# Mosfet_Board.net
KiCad netlist of a schematic drawn in Altium Designer
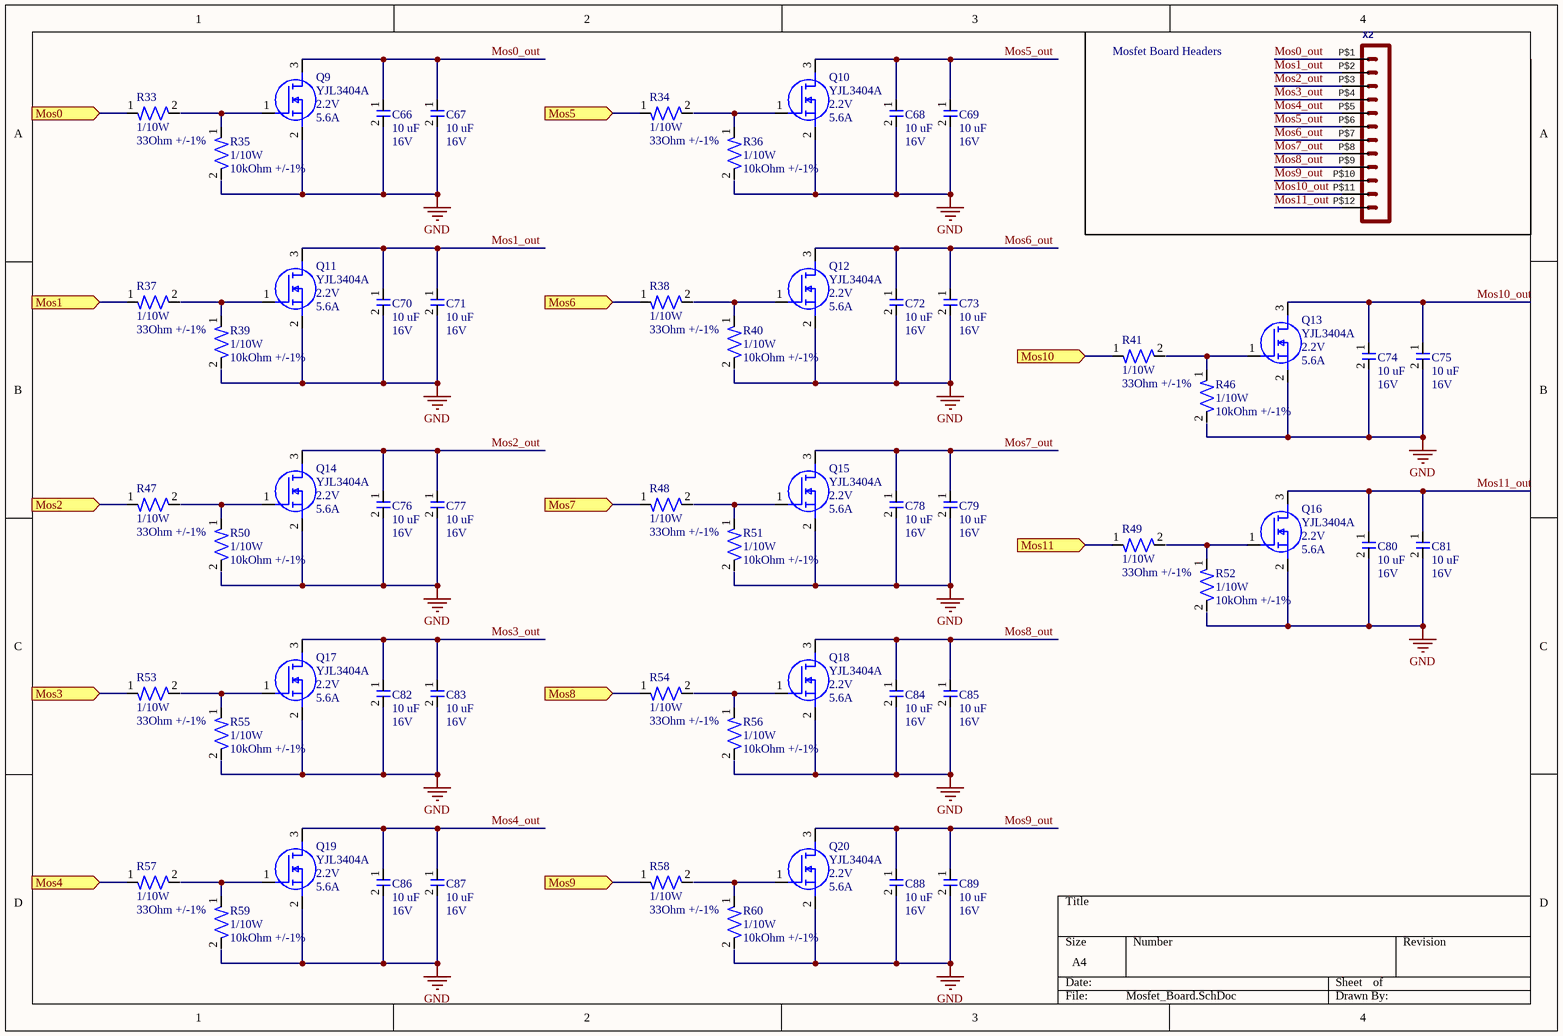
[diagram p0: Mosfet_Board.SchDoc]

(export (version "E")
  (design (tool "Eeschema 10.0.6"))
  (components
    (comp (ref "C66")
      (value "MCS1802GS-20-Z")
      (footprint "CAP-0805")
      (description "10 µF ±10% 16V Ceramic Capacitor X7R 0805 (2012 Metric)")
      (fields (field (name "CAPACITANCE") "10 uF") (field (name "VOLTAGE RATING") "16V"))
      (libsource (lib "MasterLib") (part "CAP-10U-0002"))
    )
    (comp (ref "C67")
      (value "MCS1802GS-20-Z")
      (footprint "CAP-0805")
      (description "10 µF ±10% 16V Ceramic Capacitor X7R 0805 (2012 Metric)")
      (fields (field (name "CAPACITANCE") "10 uF") (field (name "VOLTAGE RATING") "16V"))
      (libsource (lib "MasterLib") (part "CAP-10U-0002"))
    )
    (comp (ref "C68")
      (value "MCS1802GS-20-Z")
      (footprint "CAP-0805")
      (description "10 µF ±10% 16V Ceramic Capacitor X7R 0805 (2012 Metric)")
      (fields (field (name "CAPACITANCE") "10 uF") (field (name "VOLTAGE RATING") "16V"))
      (libsource (lib "MasterLib") (part "CAP-10U-0002"))
    )
    (comp (ref "C69")
      (value "MCS1802GS-20-Z")
      (footprint "CAP-0805")
      (description "10 µF ±10% 16V Ceramic Capacitor X7R 0805 (2012 Metric)")
      (fields (field (name "CAPACITANCE") "10 uF") (field (name "VOLTAGE RATING") "16V"))
      (libsource (lib "MasterLib") (part "CAP-10U-0002"))
    )
    (comp (ref "C70")
      (value "MCS1802GS-20-Z")
      (footprint "CAP-0805")
      (description "10 µF ±10% 16V Ceramic Capacitor X7R 0805 (2012 Metric)")
      (fields (field (name "CAPACITANCE") "10 uF") (field (name "VOLTAGE RATING") "16V"))
      (libsource (lib "MasterLib") (part "CAP-10U-0002"))
    )
    (comp (ref "C71")
      (value "MCS1802GS-20-Z")
      (footprint "CAP-0805")
      (description "10 µF ±10% 16V Ceramic Capacitor X7R 0805 (2012 Metric)")
      (fields (field (name "CAPACITANCE") "10 uF") (field (name "VOLTAGE RATING") "16V"))
      (libsource (lib "MasterLib") (part "CAP-10U-0002"))
    )
    (comp (ref "C72")
      (value "MCS1802GS-20-Z")
      (footprint "CAP-0805")
      (description "10 µF ±10% 16V Ceramic Capacitor X7R 0805 (2012 Metric)")
      (fields (field (name "CAPACITANCE") "10 uF") (field (name "VOLTAGE RATING") "16V"))
      (libsource (lib "MasterLib") (part "CAP-10U-0002"))
    )
    (comp (ref "C73")
      (value "MCS1802GS-20-Z")
      (footprint "CAP-0805")
      (description "10 µF ±10% 16V Ceramic Capacitor X7R 0805 (2012 Metric)")
      (fields (field (name "CAPACITANCE") "10 uF") (field (name "VOLTAGE RATING") "16V"))
      (libsource (lib "MasterLib") (part "CAP-10U-0002"))
    )
    (comp (ref "C74")
      (value "MCS1802GS-20-Z")
      (footprint "CAP-0805")
      (description "10 µF ±10% 16V Ceramic Capacitor X7R 0805 (2012 Metric)")
      (fields (field (name "CAPACITANCE") "10 uF") (field (name "VOLTAGE RATING") "16V"))
      (libsource (lib "MasterLib") (part "CAP-10U-0002"))
    )
    (comp (ref "C75")
      (value "MCS1802GS-20-Z")
      (footprint "CAP-0805")
      (description "10 µF ±10% 16V Ceramic Capacitor X7R 0805 (2012 Metric)")
      (fields (field (name "CAPACITANCE") "10 uF") (field (name "VOLTAGE RATING") "16V"))
      (libsource (lib "MasterLib") (part "CAP-10U-0002"))
    )
    (comp (ref "C76")
      (value "MCS1802GS-20-Z")
      (footprint "CAP-0805")
      (description "10 µF ±10% 16V Ceramic Capacitor X7R 0805 (2012 Metric)")
      (fields (field (name "CAPACITANCE") "10 uF") (field (name "VOLTAGE RATING") "16V"))
      (libsource (lib "MasterLib") (part "CAP-10U-0002"))
    )
    (comp (ref "C77")
      (value "MCS1802GS-20-Z")
      (footprint "CAP-0805")
      (description "10 µF ±10% 16V Ceramic Capacitor X7R 0805 (2012 Metric)")
      (fields (field (name "CAPACITANCE") "10 uF") (field (name "VOLTAGE RATING") "16V"))
      (libsource (lib "MasterLib") (part "CAP-10U-0002"))
    )
    (comp (ref "C78")
      (value "MCS1802GS-20-Z")
      (footprint "CAP-0805")
      (description "10 µF ±10% 16V Ceramic Capacitor X7R 0805 (2012 Metric)")
      (fields (field (name "CAPACITANCE") "10 uF") (field (name "VOLTAGE RATING") "16V"))
      (libsource (lib "MasterLib") (part "CAP-10U-0002"))
    )
    (comp (ref "C79")
      (value "MCS1802GS-20-Z")
      (footprint "CAP-0805")
      (description "10 µF ±10% 16V Ceramic Capacitor X7R 0805 (2012 Metric)")
      (fields (field (name "CAPACITANCE") "10 uF") (field (name "VOLTAGE RATING") "16V"))
      (libsource (lib "MasterLib") (part "CAP-10U-0002"))
    )
    (comp (ref "C80")
      (value "MCS1802GS-20-Z")
      (footprint "CAP-0805")
      (description "10 µF ±10% 16V Ceramic Capacitor X7R 0805 (2012 Metric)")
      (fields (field (name "CAPACITANCE") "10 uF") (field (name "VOLTAGE RATING") "16V"))
      (libsource (lib "MasterLib") (part "CAP-10U-0002"))
    )
    (comp (ref "C81")
      (value "MCS1802GS-20-Z")
      (footprint "CAP-0805")
      (description "10 µF ±10% 16V Ceramic Capacitor X7R 0805 (2012 Metric)")
      (fields (field (name "CAPACITANCE") "10 uF") (field (name "VOLTAGE RATING") "16V"))
      (libsource (lib "MasterLib") (part "CAP-10U-0002"))
    )
    (comp (ref "C82")
      (value "MCS1802GS-20-Z")
      (footprint "CAP-0805")
      (description "10 µF ±10% 16V Ceramic Capacitor X7R 0805 (2012 Metric)")
      (fields (field (name "CAPACITANCE") "10 uF") (field (name "VOLTAGE RATING") "16V"))
      (libsource (lib "MasterLib") (part "CAP-10U-0002"))
    )
    (comp (ref "C83")
      (value "MCS1802GS-20-Z")
      (footprint "CAP-0805")
      (description "10 µF ±10% 16V Ceramic Capacitor X7R 0805 (2012 Metric)")
      (fields (field (name "CAPACITANCE") "10 uF") (field (name "VOLTAGE RATING") "16V"))
      (libsource (lib "MasterLib") (part "CAP-10U-0002"))
    )
    (comp (ref "C84")
      (value "MCS1802GS-20-Z")
      (footprint "CAP-0805")
      (description "10 µF ±10% 16V Ceramic Capacitor X7R 0805 (2012 Metric)")
      (fields (field (name "CAPACITANCE") "10 uF") (field (name "VOLTAGE RATING") "16V"))
      (libsource (lib "MasterLib") (part "CAP-10U-0002"))
    )
    (comp (ref "C85")
      (value "MCS1802GS-20-Z")
      (footprint "CAP-0805")
      (description "10 µF ±10% 16V Ceramic Capacitor X7R 0805 (2012 Metric)")
      (fields (field (name "CAPACITANCE") "10 uF") (field (name "VOLTAGE RATING") "16V"))
      (libsource (lib "MasterLib") (part "CAP-10U-0002"))
    )
    (comp (ref "C86")
      (value "MCS1802GS-20-Z")
      (footprint "CAP-0805")
      (description "10 µF ±10% 16V Ceramic Capacitor X7R 0805 (2012 Metric)")
      (fields (field (name "CAPACITANCE") "10 uF") (field (name "VOLTAGE RATING") "16V"))
      (libsource (lib "MasterLib") (part "CAP-10U-0002"))
    )
    (comp (ref "C87")
      (value "MCS1802GS-20-Z")
      (footprint "CAP-0805")
      (description "10 µF ±10% 16V Ceramic Capacitor X7R 0805 (2012 Metric)")
      (fields (field (name "CAPACITANCE") "10 uF") (field (name "VOLTAGE RATING") "16V"))
      (libsource (lib "MasterLib") (part "CAP-10U-0002"))
    )
    (comp (ref "C88")
      (value "MCS1802GS-20-Z")
      (footprint "CAP-0805")
      (description "10 µF ±10% 16V Ceramic Capacitor X7R 0805 (2012 Metric)")
      (fields (field (name "CAPACITANCE") "10 uF") (field (name "VOLTAGE RATING") "16V"))
      (libsource (lib "MasterLib") (part "CAP-10U-0002"))
    )
    (comp (ref "C89")
      (value "MCS1802GS-20-Z")
      (footprint "CAP-0805")
      (description "10 µF ±10% 16V Ceramic Capacitor X7R 0805 (2012 Metric)")
      (fields (field (name "CAPACITANCE") "10 uF") (field (name "VOLTAGE RATING") "16V"))
      (libsource (lib "MasterLib") (part "CAP-10U-0002"))
    )
    (comp (ref "Q9")
      (value "YJL3404A")
      (footprint "NMOS-SOT23-3")
      (description "N-Channel 30 V 5.6A (Ta) 1.2W (Ta) Surface Mount SOT-23")
      (fields (field (name "VGS(TH)") "2.2V") (field (name "DRAIN CURRENT") "5.6A"))
      (libsource (lib "MasterLib") (part "NMOS-5.6A-0001"))
    )
    (comp (ref "Q10")
      (value "YJL3404A")
      (footprint "NMOS-SOT23-3")
      (description "N-Channel 30 V 5.6A (Ta) 1.2W (Ta) Surface Mount SOT-23")
      (fields (field (name "VGS(TH)") "2.2V") (field (name "DRAIN CURRENT") "5.6A"))
      (libsource (lib "MasterLib") (part "NMOS-5.6A-0001"))
    )
    (comp (ref "Q11")
      (value "YJL3404A")
      (footprint "NMOS-SOT23-3")
      (description "N-Channel 30 V 5.6A (Ta) 1.2W (Ta) Surface Mount SOT-23")
      (fields (field (name "VGS(TH)") "2.2V") (field (name "DRAIN CURRENT") "5.6A"))
      (libsource (lib "MasterLib") (part "NMOS-5.6A-0001"))
    )
    (comp (ref "Q12")
      (value "YJL3404A")
      (footprint "NMOS-SOT23-3")
      (description "N-Channel 30 V 5.6A (Ta) 1.2W (Ta) Surface Mount SOT-23")
      (fields (field (name "VGS(TH)") "2.2V") (field (name "DRAIN CURRENT") "5.6A"))
      (libsource (lib "MasterLib") (part "NMOS-5.6A-0001"))
    )
    (comp (ref "Q13")
      (value "YJL3404A")
      (footprint "NMOS-SOT23-3")
      (description "N-Channel 30 V 5.6A (Ta) 1.2W (Ta) Surface Mount SOT-23")
      (fields (field (name "VGS(TH)") "2.2V") (field (name "DRAIN CURRENT") "5.6A"))
      (libsource (lib "MasterLib") (part "NMOS-5.6A-0001"))
    )
    (comp (ref "Q14")
      (value "YJL3404A")
      (footprint "NMOS-SOT23-3")
      (description "N-Channel 30 V 5.6A (Ta) 1.2W (Ta) Surface Mount SOT-23")
      (fields (field (name "VGS(TH)") "2.2V") (field (name "DRAIN CURRENT") "5.6A"))
      (libsource (lib "MasterLib") (part "NMOS-5.6A-0001"))
    )
    (comp (ref "Q15")
      (value "YJL3404A")
      (footprint "NMOS-SOT23-3")
      (description "N-Channel 30 V 5.6A (Ta) 1.2W (Ta) Surface Mount SOT-23")
      (fields (field (name "VGS(TH)") "2.2V") (field (name "DRAIN CURRENT") "5.6A"))
      (libsource (lib "MasterLib") (part "NMOS-5.6A-0001"))
    )
    (comp (ref "Q16")
      (value "YJL3404A")
      (footprint "NMOS-SOT23-3")
      (description "N-Channel 30 V 5.6A (Ta) 1.2W (Ta) Surface Mount SOT-23")
      (fields (field (name "VGS(TH)") "2.2V") (field (name "DRAIN CURRENT") "5.6A"))
      (libsource (lib "MasterLib") (part "NMOS-5.6A-0001"))
    )
    (comp (ref "Q17")
      (value "YJL3404A")
      (footprint "NMOS-SOT23-3")
      (description "N-Channel 30 V 5.6A (Ta) 1.2W (Ta) Surface Mount SOT-23")
      (fields (field (name "VGS(TH)") "2.2V") (field (name "DRAIN CURRENT") "5.6A"))
      (libsource (lib "MasterLib") (part "NMOS-5.6A-0001"))
    )
    (comp (ref "Q18")
      (value "YJL3404A")
      (footprint "NMOS-SOT23-3")
      (description "N-Channel 30 V 5.6A (Ta) 1.2W (Ta) Surface Mount SOT-23")
      (fields (field (name "VGS(TH)") "2.2V") (field (name "DRAIN CURRENT") "5.6A"))
      (libsource (lib "MasterLib") (part "NMOS-5.6A-0001"))
    )
    (comp (ref "Q19")
      (value "YJL3404A")
      (footprint "NMOS-SOT23-3")
      (description "N-Channel 30 V 5.6A (Ta) 1.2W (Ta) Surface Mount SOT-23")
      (fields (field (name "VGS(TH)") "2.2V") (field (name "DRAIN CURRENT") "5.6A"))
      (libsource (lib "MasterLib") (part "NMOS-5.6A-0001"))
    )
    (comp (ref "Q20")
      (value "YJL3404A")
      (footprint "NMOS-SOT23-3")
      (description "N-Channel 30 V 5.6A (Ta) 1.2W (Ta) Surface Mount SOT-23")
      (fields (field (name "VGS(TH)") "2.2V") (field (name "DRAIN CURRENT") "5.6A"))
      (libsource (lib "MasterLib") (part "NMOS-5.6A-0001"))
    )
    (comp (ref "R33")
      (value "RC0603FR-0733RP")
      (footprint "RES-0603")
      (description "RES SMD 33 OHM 1% 1/10W 0603")
      (fields
        (field (name "MANUFACTURER") "YAGEO")
        (field (name "POWER RATING") "1/10W")
        (field (name "RESISTANCE") "33Ohm +/-1%")
      )
      (libsource (lib "MasterLib") (part "RES-33-0002"))
    )
    (comp (ref "R34")
      (value "RC0603FR-0733RP")
      (footprint "RES-0603")
      (description "RES SMD 33 OHM 1% 1/10W 0603")
      (fields
        (field (name "MANUFACTURER") "YAGEO")
        (field (name "POWER RATING") "1/10W")
        (field (name "RESISTANCE") "33Ohm +/-1%")
      )
      (libsource (lib "MasterLib") (part "RES-33-0002"))
    )
    (comp (ref "R35")
      (value "RC0603FR-0710KP")
      (footprint "RES-0603")
      (description "RES SMD 10K OHM 1% 1/10W 0603")
      (fields
        (field (name "MANUFACTURER") "YAGEO")
        (field (name "POWER RATING") "1/10W")
        (field (name "RESISTANCE") "10kOhm +/-1%")
      )
      (libsource (lib "MasterLib") (part "RES-10K-0002"))
    )
    (comp (ref "R36")
      (value "RC0603FR-0710KP")
      (footprint "RES-0603")
      (description "RES SMD 10K OHM 1% 1/10W 0603")
      (fields
        (field (name "MANUFACTURER") "YAGEO")
        (field (name "POWER RATING") "1/10W")
        (field (name "RESISTANCE") "10kOhm +/-1%")
      )
      (libsource (lib "MasterLib") (part "RES-10K-0002"))
    )
    (comp (ref "R37")
      (value "RC0603FR-0733RP")
      (footprint "RES-0603")
      (description "RES SMD 33 OHM 1% 1/10W 0603")
      (fields
        (field (name "MANUFACTURER") "YAGEO")
        (field (name "POWER RATING") "1/10W")
        (field (name "RESISTANCE") "33Ohm +/-1%")
      )
      (libsource (lib "MasterLib") (part "RES-33-0002"))
    )
    (comp (ref "R38")
      (value "RC0603FR-0733RP")
      (footprint "RES-0603")
      (description "RES SMD 33 OHM 1% 1/10W 0603")
      (fields
        (field (name "MANUFACTURER") "YAGEO")
        (field (name "POWER RATING") "1/10W")
        (field (name "RESISTANCE") "33Ohm +/-1%")
      )
      (libsource (lib "MasterLib") (part "RES-33-0002"))
    )
    (comp (ref "R39")
      (value "RC0603FR-0710KP")
      (footprint "RES-0603")
      (description "RES SMD 10K OHM 1% 1/10W 0603")
      (fields
        (field (name "MANUFACTURER") "YAGEO")
        (field (name "POWER RATING") "1/10W")
        (field (name "RESISTANCE") "10kOhm +/-1%")
      )
      (libsource (lib "MasterLib") (part "RES-10K-0002"))
    )
    (comp (ref "R40")
      (value "RC0603FR-0710KP")
      (footprint "RES-0603")
      (description "RES SMD 10K OHM 1% 1/10W 0603")
      (fields
        (field (name "MANUFACTURER") "YAGEO")
        (field (name "POWER RATING") "1/10W")
        (field (name "RESISTANCE") "10kOhm +/-1%")
      )
      (libsource (lib "MasterLib") (part "RES-10K-0002"))
    )
    (comp (ref "R41")
      (value "RC0603FR-0733RP")
      (footprint "RES-0603")
      (description "RES SMD 33 OHM 1% 1/10W 0603")
      (fields
        (field (name "MANUFACTURER") "YAGEO")
        (field (name "POWER RATING") "1/10W")
        (field (name "RESISTANCE") "33Ohm +/-1%")
      )
      (libsource (lib "MasterLib") (part "RES-33-0002"))
    )
    (comp (ref "R46")
      (value "RC0603FR-0710KP")
      (footprint "RES-0603")
      (description "RES SMD 10K OHM 1% 1/10W 0603")
      (fields
        (field (name "MANUFACTURER") "YAGEO")
        (field (name "POWER RATING") "1/10W")
        (field (name "RESISTANCE") "10kOhm +/-1%")
      )
      (libsource (lib "MasterLib") (part "RES-10K-0002"))
    )
    (comp (ref "R47")
      (value "RC0603FR-0733RP")
      (footprint "RES-0603")
      (description "RES SMD 33 OHM 1% 1/10W 0603")
      (fields
        (field (name "MANUFACTURER") "YAGEO")
        (field (name "POWER RATING") "1/10W")
        (field (name "RESISTANCE") "33Ohm +/-1%")
      )
      (libsource (lib "MasterLib") (part "RES-33-0002"))
    )
    (comp (ref "R48")
      (value "RC0603FR-0733RP")
      (footprint "RES-0603")
      (description "RES SMD 33 OHM 1% 1/10W 0603")
      (fields
        (field (name "MANUFACTURER") "YAGEO")
        (field (name "POWER RATING") "1/10W")
        (field (name "RESISTANCE") "33Ohm +/-1%")
      )
      (libsource (lib "MasterLib") (part "RES-33-0002"))
    )
    (comp (ref "R49")
      (value "RC0603FR-0733RP")
      (footprint "RES-0603")
      (description "RES SMD 33 OHM 1% 1/10W 0603")
      (fields
        (field (name "MANUFACTURER") "YAGEO")
        (field (name "POWER RATING") "1/10W")
        (field (name "RESISTANCE") "33Ohm +/-1%")
      )
      (libsource (lib "MasterLib") (part "RES-33-0002"))
    )
    (comp (ref "R50")
      (value "RC0603FR-0710KP")
      (footprint "RES-0603")
      (description "RES SMD 10K OHM 1% 1/10W 0603")
      (fields
        (field (name "MANUFACTURER") "YAGEO")
        (field (name "POWER RATING") "1/10W")
        (field (name "RESISTANCE") "10kOhm +/-1%")
      )
      (libsource (lib "MasterLib") (part "RES-10K-0002"))
    )
    (comp (ref "R51")
      (value "RC0603FR-0710KP")
      (footprint "RES-0603")
      (description "RES SMD 10K OHM 1% 1/10W 0603")
      (fields
        (field (name "MANUFACTURER") "YAGEO")
        (field (name "POWER RATING") "1/10W")
        (field (name "RESISTANCE") "10kOhm +/-1%")
      )
      (libsource (lib "MasterLib") (part "RES-10K-0002"))
    )
    (comp (ref "R52")
      (value "RC0603FR-0710KP")
      (footprint "RES-0603")
      (description "RES SMD 10K OHM 1% 1/10W 0603")
      (fields
        (field (name "MANUFACTURER") "YAGEO")
        (field (name "POWER RATING") "1/10W")
        (field (name "RESISTANCE") "10kOhm +/-1%")
      )
      (libsource (lib "MasterLib") (part "RES-10K-0002"))
    )
    (comp (ref "R53")
      (value "RC0603FR-0733RP")
      (footprint "RES-0603")
      (description "RES SMD 33 OHM 1% 1/10W 0603")
      (fields
        (field (name "MANUFACTURER") "YAGEO")
        (field (name "POWER RATING") "1/10W")
        (field (name "RESISTANCE") "33Ohm +/-1%")
      )
      (libsource (lib "MasterLib") (part "RES-33-0002"))
    )
    (comp (ref "R54")
      (value "RC0603FR-0733RP")
      (footprint "RES-0603")
      (description "RES SMD 33 OHM 1% 1/10W 0603")
      (fields
        (field (name "MANUFACTURER") "YAGEO")
        (field (name "POWER RATING") "1/10W")
        (field (name "RESISTANCE") "33Ohm +/-1%")
      )
      (libsource (lib "MasterLib") (part "RES-33-0002"))
    )
    (comp (ref "R55")
      (value "RC0603FR-0710KP")
      (footprint "RES-0603")
      (description "RES SMD 10K OHM 1% 1/10W 0603")
      (fields
        (field (name "MANUFACTURER") "YAGEO")
        (field (name "POWER RATING") "1/10W")
        (field (name "RESISTANCE") "10kOhm +/-1%")
      )
      (libsource (lib "MasterLib") (part "RES-10K-0002"))
    )
    (comp (ref "R56")
      (value "RC0603FR-0710KP")
      (footprint "RES-0603")
      (description "RES SMD 10K OHM 1% 1/10W 0603")
      (fields
        (field (name "MANUFACTURER") "YAGEO")
        (field (name "POWER RATING") "1/10W")
        (field (name "RESISTANCE") "10kOhm +/-1%")
      )
      (libsource (lib "MasterLib") (part "RES-10K-0002"))
    )
    (comp (ref "R57")
      (value "RC0603FR-0733RP")
      (footprint "RES-0603")
      (description "RES SMD 33 OHM 1% 1/10W 0603")
      (fields
        (field (name "MANUFACTURER") "YAGEO")
        (field (name "POWER RATING") "1/10W")
        (field (name "RESISTANCE") "33Ohm +/-1%")
      )
      (libsource (lib "MasterLib") (part "RES-33-0002"))
    )
    (comp (ref "R58")
      (value "RC0603FR-0733RP")
      (footprint "RES-0603")
      (description "RES SMD 33 OHM 1% 1/10W 0603")
      (fields
        (field (name "MANUFACTURER") "YAGEO")
        (field (name "POWER RATING") "1/10W")
        (field (name "RESISTANCE") "33Ohm +/-1%")
      )
      (libsource (lib "MasterLib") (part "RES-33-0002"))
    )
    (comp (ref "R59")
      (value "RC0603FR-0710KP")
      (footprint "RES-0603")
      (description "RES SMD 10K OHM 1% 1/10W 0603")
      (fields
        (field (name "MANUFACTURER") "YAGEO")
        (field (name "POWER RATING") "1/10W")
        (field (name "RESISTANCE") "10kOhm +/-1%")
      )
      (libsource (lib "MasterLib") (part "RES-10K-0002"))
    )
    (comp (ref "R60")
      (value "RC0603FR-0710KP")
      (footprint "RES-0603")
      (description "RES SMD 10K OHM 1% 1/10W 0603")
      (fields
        (field (name "MANUFACTURER") "YAGEO")
        (field (name "POWER RATING") "1/10W")
        (field (name "RESISTANCE") "10kOhm +/-1%")
      )
      (libsource (lib "MasterLib") (part "RES-10K-0002"))
    )
    (comp (ref "X2")
      (value "Molex - Micro-Fit 3.0 Series connector,  3.00mm (0.118\") pitch header, 12 positions.")
      (footprint "44764-1201")
      (libsource (lib "Molex Microfit") (part "HEADER_POS12_?44764-1201"))
    )
  )
  (nets
    (net (code "1") (name "/Mos0") (class "Default")
      (node (ref "R33") (pin "1") (pinfunction "1_1") (pintype "passive"))
    )
    (net (code "2") (name "/Mos0_out") (class "Default")
      (node (ref "C66") (pin "1") (pinfunction "1_1") (pintype "passive"))
      (node (ref "C67") (pin "1") (pinfunction "1_1") (pintype "passive"))
      (node (ref "Q9") (pin "3") (pinfunction "D_3") (pintype "passive"))
      (node (ref "X2") (pin "P$1") (pinfunction "1_P$1") (pintype "passive"))
    )
    (net (code "3") (name "/Mos1") (class "Default")
      (node (ref "R37") (pin "1") (pinfunction "1_1") (pintype "passive"))
    )
    (net (code "4") (name "/Mos1_out") (class "Default")
      (node (ref "C70") (pin "1") (pinfunction "1_1") (pintype "passive"))
      (node (ref "C71") (pin "1") (pinfunction "1_1") (pintype "passive"))
      (node (ref "Q11") (pin "3") (pinfunction "D_3") (pintype "passive"))
      (node (ref "X2") (pin "P$2") (pinfunction "2_P$2") (pintype "passive"))
    )
    (net (code "5") (name "/Mos2") (class "Default")
      (node (ref "R47") (pin "1") (pinfunction "1_1") (pintype "passive"))
    )
    (net (code "6") (name "/Mos2_out") (class "Default")
      (node (ref "C76") (pin "1") (pinfunction "1_1") (pintype "passive"))
      (node (ref "C77") (pin "1") (pinfunction "1_1") (pintype "passive"))
      (node (ref "Q14") (pin "3") (pinfunction "D_3") (pintype "passive"))
      (node (ref "X2") (pin "P$3") (pinfunction "3_P$3") (pintype "passive"))
    )
    (net (code "7") (name "/Mos3") (class "Default")
      (node (ref "R53") (pin "1") (pinfunction "1_1") (pintype "passive"))
    )
    (net (code "8") (name "/Mos3_out") (class "Default")
      (node (ref "C82") (pin "1") (pinfunction "1_1") (pintype "passive"))
      (node (ref "C83") (pin "1") (pinfunction "1_1") (pintype "passive"))
      (node (ref "Q17") (pin "3") (pinfunction "D_3") (pintype "passive"))
      (node (ref "X2") (pin "P$4") (pinfunction "4_P$4") (pintype "passive"))
    )
    (net (code "9") (name "/Mos4") (class "Default")
      (node (ref "R57") (pin "1") (pinfunction "1_1") (pintype "passive"))
    )
    (net (code "10") (name "/Mos4_out") (class "Default")
      (node (ref "C86") (pin "1") (pinfunction "1_1") (pintype "passive"))
      (node (ref "C87") (pin "1") (pinfunction "1_1") (pintype "passive"))
      (node (ref "Q19") (pin "3") (pinfunction "D_3") (pintype "passive"))
      (node (ref "X2") (pin "P$5") (pinfunction "5_P$5") (pintype "passive"))
    )
    (net (code "11") (name "/Mos5") (class "Default")
      (node (ref "R34") (pin "1") (pinfunction "1_1") (pintype "passive"))
    )
    (net (code "12") (name "/Mos5_out") (class "Default")
      (node (ref "C68") (pin "1") (pinfunction "1_1") (pintype "passive"))
      (node (ref "C69") (pin "1") (pinfunction "1_1") (pintype "passive"))
      (node (ref "Q10") (pin "3") (pinfunction "D_3") (pintype "passive"))
      (node (ref "X2") (pin "P$6") (pinfunction "6_P$6") (pintype "passive"))
    )
    (net (code "13") (name "/Mos6") (class "Default")
      (node (ref "R38") (pin "1") (pinfunction "1_1") (pintype "passive"))
    )
    (net (code "14") (name "/Mos6_out") (class "Default")
      (node (ref "C72") (pin "1") (pinfunction "1_1") (pintype "passive"))
      (node (ref "C73") (pin "1") (pinfunction "1_1") (pintype "passive"))
      (node (ref "Q12") (pin "3") (pinfunction "D_3") (pintype "passive"))
      (node (ref "X2") (pin "P$7") (pinfunction "7_P$7") (pintype "passive"))
    )
    (net (code "15") (name "/Mos7") (class "Default")
      (node (ref "R48") (pin "1") (pinfunction "1_1") (pintype "passive"))
    )
    (net (code "16") (name "/Mos7_out") (class "Default")
      (node (ref "C78") (pin "1") (pinfunction "1_1") (pintype "passive"))
      (node (ref "C79") (pin "1") (pinfunction "1_1") (pintype "passive"))
      (node (ref "Q15") (pin "3") (pinfunction "D_3") (pintype "passive"))
      (node (ref "X2") (pin "P$8") (pinfunction "8_P$8") (pintype "passive"))
    )
    (net (code "17") (name "/Mos8") (class "Default")
      (node (ref "R54") (pin "1") (pinfunction "1_1") (pintype "passive"))
    )
    (net (code "18") (name "/Mos8_out") (class "Default")
      (node (ref "C84") (pin "1") (pinfunction "1_1") (pintype "passive"))
      (node (ref "C85") (pin "1") (pinfunction "1_1") (pintype "passive"))
      (node (ref "Q18") (pin "3") (pinfunction "D_3") (pintype "passive"))
      (node (ref "X2") (pin "P$9") (pinfunction "9_P$9") (pintype "passive"))
    )
    (net (code "19") (name "/Mos9") (class "Default")
      (node (ref "R58") (pin "1") (pinfunction "1_1") (pintype "passive"))
    )
    (net (code "20") (name "/Mos9_out") (class "Default")
      (node (ref "C88") (pin "1") (pinfunction "1_1") (pintype "passive"))
      (node (ref "C89") (pin "1") (pinfunction "1_1") (pintype "passive"))
      (node (ref "Q20") (pin "3") (pinfunction "D_3") (pintype "passive"))
      (node (ref "X2") (pin "P$10") (pinfunction "10_P$10") (pintype "passive"))
    )
    (net (code "21") (name "/Mos10") (class "Default")
      (node (ref "R41") (pin "1") (pinfunction "1_1") (pintype "passive"))
    )
    (net (code "22") (name "/Mos10_out") (class "Default")
      (node (ref "C74") (pin "1") (pinfunction "1_1") (pintype "passive"))
      (node (ref "C75") (pin "1") (pinfunction "1_1") (pintype "passive"))
      (node (ref "Q13") (pin "3") (pinfunction "D_3") (pintype "passive"))
      (node (ref "X2") (pin "P$11") (pinfunction "11_P$11") (pintype "passive"))
    )
    (net (code "23") (name "/Mos11") (class "Default")
      (node (ref "R49") (pin "1") (pinfunction "1_1") (pintype "passive"))
    )
    (net (code "24") (name "/Mos11_out") (class "Default")
      (node (ref "C80") (pin "1") (pinfunction "1_1") (pintype "passive"))
      (node (ref "C81") (pin "1") (pinfunction "1_1") (pintype "passive"))
      (node (ref "Q16") (pin "3") (pinfunction "D_3") (pintype "passive"))
      (node (ref "X2") (pin "P$12") (pinfunction "12_P$12") (pintype "passive"))
    )
    (net (code "25") (name "GND") (class "Default")
      (node (ref "C66") (pin "2") (pinfunction "2_2") (pintype "passive"))
      (node (ref "C67") (pin "2") (pinfunction "2_2") (pintype "passive"))
      (node (ref "C68") (pin "2") (pinfunction "2_2") (pintype "passive"))
      (node (ref "C69") (pin "2") (pinfunction "2_2") (pintype "passive"))
      (node (ref "C70") (pin "2") (pinfunction "2_2") (pintype "passive"))
      (node (ref "C71") (pin "2") (pinfunction "2_2") (pintype "passive"))
      (node (ref "C72") (pin "2") (pinfunction "2_2") (pintype "passive"))
      (node (ref "C73") (pin "2") (pinfunction "2_2") (pintype "passive"))
      (node (ref "C74") (pin "2") (pinfunction "2_2") (pintype "passive"))
      (node (ref "C75") (pin "2") (pinfunction "2_2") (pintype "passive"))
      (node (ref "C76") (pin "2") (pinfunction "2_2") (pintype "passive"))
      (node (ref "C77") (pin "2") (pinfunction "2_2") (pintype "passive"))
      (node (ref "C78") (pin "2") (pinfunction "2_2") (pintype "passive"))
      (node (ref "C79") (pin "2") (pinfunction "2_2") (pintype "passive"))
      (node (ref "C80") (pin "2") (pinfunction "2_2") (pintype "passive"))
      (node (ref "C81") (pin "2") (pinfunction "2_2") (pintype "passive"))
      (node (ref "C82") (pin "2") (pinfunction "2_2") (pintype "passive"))
      (node (ref "C83") (pin "2") (pinfunction "2_2") (pintype "passive"))
      (node (ref "C84") (pin "2") (pinfunction "2_2") (pintype "passive"))
      (node (ref "C85") (pin "2") (pinfunction "2_2") (pintype "passive"))
      (node (ref "C86") (pin "2") (pinfunction "2_2") (pintype "passive"))
      (node (ref "C87") (pin "2") (pinfunction "2_2") (pintype "passive"))
      (node (ref "C88") (pin "2") (pinfunction "2_2") (pintype "passive"))
      (node (ref "C89") (pin "2") (pinfunction "2_2") (pintype "passive"))
      (node (ref "Q10") (pin "2") (pinfunction "S_2") (pintype "passive"))
      (node (ref "Q11") (pin "2") (pinfunction "S_2") (pintype "passive"))
      (node (ref "Q12") (pin "2") (pinfunction "S_2") (pintype "passive"))
      (node (ref "Q13") (pin "2") (pinfunction "S_2") (pintype "passive"))
      (node (ref "Q14") (pin "2") (pinfunction "S_2") (pintype "passive"))
      (node (ref "Q15") (pin "2") (pinfunction "S_2") (pintype "passive"))
      (node (ref "Q16") (pin "2") (pinfunction "S_2") (pintype "passive"))
      (node (ref "Q17") (pin "2") (pinfunction "S_2") (pintype "passive"))
      (node (ref "Q18") (pin "2") (pinfunction "S_2") (pintype "passive"))
      (node (ref "Q19") (pin "2") (pinfunction "S_2") (pintype "passive"))
      (node (ref "Q20") (pin "2") (pinfunction "S_2") (pintype "passive"))
      (node (ref "Q9") (pin "2") (pinfunction "S_2") (pintype "passive"))
    )
    (net (code "26") (name "Net-(Q9-G)") (class "Default")
      (node (ref "Q9") (pin "1") (pinfunction "G_1") (pintype "passive"))
      (node (ref "R35") (pin "1") (pinfunction "1_1") (pintype "passive"))
    )
    (net (code "27") (name "Net-(Q10-G)") (class "Default")
      (node (ref "Q10") (pin "1") (pinfunction "G_1") (pintype "passive"))
      (node (ref "R36") (pin "1") (pinfunction "1_1") (pintype "passive"))
    )
    (net (code "28") (name "Net-(Q11-G)") (class "Default")
      (node (ref "Q11") (pin "1") (pinfunction "G_1") (pintype "passive"))
      (node (ref "R39") (pin "1") (pinfunction "1_1") (pintype "passive"))
    )
    (net (code "29") (name "Net-(Q12-G)") (class "Default")
      (node (ref "Q12") (pin "1") (pinfunction "G_1") (pintype "passive"))
      (node (ref "R40") (pin "1") (pinfunction "1_1") (pintype "passive"))
    )
    (net (code "30") (name "Net-(Q13-G)") (class "Default")
      (node (ref "Q13") (pin "1") (pinfunction "G_1") (pintype "passive"))
      (node (ref "R46") (pin "1") (pinfunction "1_1") (pintype "passive"))
    )
    (net (code "31") (name "Net-(Q14-G)") (class "Default")
      (node (ref "Q14") (pin "1") (pinfunction "G_1") (pintype "passive"))
      (node (ref "R50") (pin "1") (pinfunction "1_1") (pintype "passive"))
    )
    (net (code "32") (name "Net-(Q15-G)") (class "Default")
      (node (ref "Q15") (pin "1") (pinfunction "G_1") (pintype "passive"))
      (node (ref "R51") (pin "1") (pinfunction "1_1") (pintype "passive"))
    )
    (net (code "33") (name "Net-(Q16-G)") (class "Default")
      (node (ref "Q16") (pin "1") (pinfunction "G_1") (pintype "passive"))
      (node (ref "R52") (pin "1") (pinfunction "1_1") (pintype "passive"))
    )
    (net (code "34") (name "Net-(Q17-G)") (class "Default")
      (node (ref "Q17") (pin "1") (pinfunction "G_1") (pintype "passive"))
      (node (ref "R55") (pin "1") (pinfunction "1_1") (pintype "passive"))
    )
    (net (code "35") (name "Net-(Q18-G)") (class "Default")
      (node (ref "Q18") (pin "1") (pinfunction "G_1") (pintype "passive"))
      (node (ref "R56") (pin "1") (pinfunction "1_1") (pintype "passive"))
    )
    (net (code "36") (name "Net-(Q19-G)") (class "Default")
      (node (ref "Q19") (pin "1") (pinfunction "G_1") (pintype "passive"))
      (node (ref "R59") (pin "1") (pinfunction "1_1") (pintype "passive"))
    )
    (net (code "37") (name "Net-(Q20-G)") (class "Default")
      (node (ref "Q20") (pin "1") (pinfunction "G_1") (pintype "passive"))
      (node (ref "R60") (pin "1") (pinfunction "1_1") (pintype "passive"))
    )
    (net (code "38") (name "unconnected-(R33-Pad2)") (class "Default")
      (node (ref "R33") (pin "2") (pinfunction "2_2") (pintype "passive"))
    )
    (net (code "39") (name "unconnected-(R34-Pad2)") (class "Default")
      (node (ref "R34") (pin "2") (pinfunction "2_2") (pintype "passive"))
    )
    (net (code "40") (name "unconnected-(R35-Pad2)") (class "Default")
      (node (ref "R35") (pin "2") (pinfunction "2_2") (pintype "passive"))
    )
    (net (code "41") (name "unconnected-(R36-Pad2)") (class "Default")
      (node (ref "R36") (pin "2") (pinfunction "2_2") (pintype "passive"))
    )
    (net (code "42") (name "unconnected-(R37-Pad2)") (class "Default")
      (node (ref "R37") (pin "2") (pinfunction "2_2") (pintype "passive"))
    )
    (net (code "43") (name "unconnected-(R38-Pad2)") (class "Default")
      (node (ref "R38") (pin "2") (pinfunction "2_2") (pintype "passive"))
    )
    (net (code "44") (name "unconnected-(R39-Pad2)") (class "Default")
      (node (ref "R39") (pin "2") (pinfunction "2_2") (pintype "passive"))
    )
    (net (code "45") (name "unconnected-(R40-Pad2)") (class "Default")
      (node (ref "R40") (pin "2") (pinfunction "2_2") (pintype "passive"))
    )
    (net (code "46") (name "unconnected-(R41-Pad2)") (class "Default")
      (node (ref "R41") (pin "2") (pinfunction "2_2") (pintype "passive"))
    )
    (net (code "47") (name "unconnected-(R46-Pad2)") (class "Default")
      (node (ref "R46") (pin "2") (pinfunction "2_2") (pintype "passive"))
    )
    (net (code "48") (name "unconnected-(R47-Pad2)") (class "Default")
      (node (ref "R47") (pin "2") (pinfunction "2_2") (pintype "passive"))
    )
    (net (code "49") (name "unconnected-(R48-Pad2)") (class "Default")
      (node (ref "R48") (pin "2") (pinfunction "2_2") (pintype "passive"))
    )
    (net (code "50") (name "unconnected-(R49-Pad2)") (class "Default")
      (node (ref "R49") (pin "2") (pinfunction "2_2") (pintype "passive"))
    )
    (net (code "51") (name "unconnected-(R50-Pad2)") (class "Default")
      (node (ref "R50") (pin "2") (pinfunction "2_2") (pintype "passive"))
    )
    (net (code "52") (name "unconnected-(R51-Pad2)") (class "Default")
      (node (ref "R51") (pin "2") (pinfunction "2_2") (pintype "passive"))
    )
    (net (code "53") (name "unconnected-(R52-Pad2)") (class "Default")
      (node (ref "R52") (pin "2") (pinfunction "2_2") (pintype "passive"))
    )
    (net (code "54") (name "unconnected-(R53-Pad2)") (class "Default")
      (node (ref "R53") (pin "2") (pinfunction "2_2") (pintype "passive"))
    )
    (net (code "55") (name "unconnected-(R54-Pad2)") (class "Default")
      (node (ref "R54") (pin "2") (pinfunction "2_2") (pintype "passive"))
    )
    (net (code "56") (name "unconnected-(R55-Pad2)") (class "Default")
      (node (ref "R55") (pin "2") (pinfunction "2_2") (pintype "passive"))
    )
    (net (code "57") (name "unconnected-(R56-Pad2)") (class "Default")
      (node (ref "R56") (pin "2") (pinfunction "2_2") (pintype "passive"))
    )
    (net (code "58") (name "unconnected-(R57-Pad2)") (class "Default")
      (node (ref "R57") (pin "2") (pinfunction "2_2") (pintype "passive"))
    )
    (net (code "59") (name "unconnected-(R58-Pad2)") (class "Default")
      (node (ref "R58") (pin "2") (pinfunction "2_2") (pintype "passive"))
    )
    (net (code "60") (name "unconnected-(R59-Pad2)") (class "Default")
      (node (ref "R59") (pin "2") (pinfunction "2_2") (pintype "passive"))
    )
    (net (code "61") (name "unconnected-(R60-Pad2)") (class "Default")
      (node (ref "R60") (pin "2") (pinfunction "2_2") (pintype "passive"))
    )
  )
)
